# EEPROM_shield.net
KiCad netlist of a schematic drawn in EAGLE
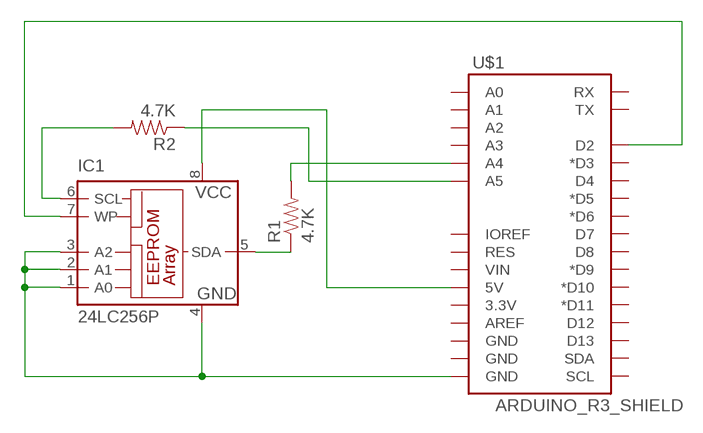
[diagram p0: schematic, sheet 1]

(export (version "E")
  (design (tool "Eeschema 10.0.6"))
  (components
    (comp (ref "IC1")
      (value "24LC256P")
      (footprint "eagle-import:DIL8")
      (fields (field (name "MF") "MICROCHIP") (field (name "MPN") "24LC256-E/P"))
      (libsource (lib "eagle-import") (part "24PLC256"))
    )
    (comp (ref "R1")
      (value "4.7K")
      (footprint "eagle-import:AXIAL-0.4")
      (libsource (lib "eagle-import") (part "RESISTORPTH-1/4W"))
    )
    (comp (ref "R2")
      (value "4.7K")
      (footprint "eagle-import:AXIAL-0.4")
      (libsource (lib "eagle-import") (part "RESISTORPTH-1/4W"))
    )
    (comp (ref "U$1")
      (value "ARDUINO_R3_SHIELD")
      (footprint "eagle-import:UNO_R3_SHIELD")
      (libsource (lib "eagle-import") (part "ARDUINO_R3_SHIELD"))
    )
  )
  (nets
    (net (code "1") (name "Net-(IC1-A0)") (class "Default")
      (node (ref "IC1") (pin "1") (pinfunction "A0_1") (pintype "input"))
      (node (ref "IC1") (pin "2") (pinfunction "A1_2") (pintype "input"))
      (node (ref "IC1") (pin "3") (pinfunction "A2_3") (pintype "input"))
      (node (ref "IC1") (pin "4") (pinfunction "GND_4") (pintype "power_in"))
      (node (ref "U$1") (pin "GND@0") (pinfunction "GND_GND@0") (pintype "bidirectional"))
    )
    (net (code "2") (name "Net-(IC1-SCL)") (class "Default")
      (node (ref "IC1") (pin "6") (pinfunction "SCL_6") (pintype "input"))
      (node (ref "R2") (pin "P$2") (pinfunction "2_P$2") (pintype "passive"))
    )
    (net (code "3") (name "Net-(IC1-SDA)") (class "Default")
      (node (ref "IC1") (pin "5") (pinfunction "SDA_5") (pintype "bidirectional"))
      (node (ref "R1") (pin "P$1") (pinfunction "1_P$1") (pintype "passive"))
    )
    (net (code "4") (name "Net-(IC1-VCC)") (class "Default")
      (node (ref "IC1") (pin "8") (pinfunction "VCC_8") (pintype "power_in"))
      (node (ref "U$1") (pin "5V") (pinfunction "5V_5V") (pintype "bidirectional"))
    )
    (net (code "5") (name "Net-(IC1-WP)") (class "Default")
      (node (ref "IC1") (pin "7") (pinfunction "WP_7") (pintype "input"))
      (node (ref "U$1") (pin "D2") (pinfunction "D2_D2") (pintype "bidirectional"))
    )
    (net (code "6") (name "Net-(R1-2)") (class "Default")
      (node (ref "R1") (pin "P$2") (pinfunction "2_P$2") (pintype "passive"))
      (node (ref "U$1") (pin "A4") (pinfunction "A4_A4") (pintype "bidirectional"))
    )
    (net (code "7") (name "Net-(R2-1)") (class "Default")
      (node (ref "R2") (pin "P$1") (pinfunction "1_P$1") (pintype "passive"))
      (node (ref "U$1") (pin "A5") (pinfunction "A5_A5") (pintype "bidirectional"))
    )
    (net (code "8") (name "unconnected-(U$1-*D3-PadD3)") (class "Default")
      (node (ref "U$1") (pin "D3") (pinfunction "*D3_D3") (pintype "bidirectional"))
    )
    (net (code "9") (name "unconnected-(U$1-*D5-PadD5)") (class "Default")
      (node (ref "U$1") (pin "D5") (pinfunction "*D5_D5") (pintype "bidirectional"))
    )
    (net (code "10") (name "unconnected-(U$1-*D6-PadD6)") (class "Default")
      (node (ref "U$1") (pin "D6") (pinfunction "*D6_D6") (pintype "bidirectional"))
    )
    (net (code "11") (name "unconnected-(U$1-*D9-PadD9)") (class "Default")
      (node (ref "U$1") (pin "D9") (pinfunction "*D9_D9") (pintype "bidirectional"))
    )
    (net (code "12") (name "unconnected-(U$1-*D10-PadD10)") (class "Default")
      (node (ref "U$1") (pin "D10") (pinfunction "*D10_D10") (pintype "bidirectional"))
    )
    (net (code "13") (name "unconnected-(U$1-*D11-PadD11)") (class "Default")
      (node (ref "U$1") (pin "D11") (pinfunction "*D11_D11") (pintype "bidirectional"))
    )
    (net (code "14") (name "unconnected-(U$1-GND-PadGND@1)") (class "Default")
      (node (ref "U$1") (pin "GND@1") (pinfunction "GND_GND@1") (pintype "bidirectional"))
    )
    (net (code "15") (name "unconnected-(U$1-GND-PadGND@2)") (class "Default")
      (node (ref "U$1") (pin "GND@2") (pinfunction "GND_GND@2") (pintype "bidirectional"))
    )
    (net (code "16") (name "unconnected-(U$1-Pad3.3V)") (class "Default")
      (node (ref "U$1") (pin "3.3V") (pinfunction "3.3V_3.3V") (pintype "bidirectional"))
    )
    (net (code "17") (name "unconnected-(U$1-PadA0)") (class "Default")
      (node (ref "U$1") (pin "A0") (pinfunction "A0_A0") (pintype "bidirectional"))
    )
    (net (code "18") (name "unconnected-(U$1-PadA1)") (class "Default")
      (node (ref "U$1") (pin "A1") (pinfunction "A1_A1") (pintype "bidirectional"))
    )
    (net (code "19") (name "unconnected-(U$1-PadA2)") (class "Default")
      (node (ref "U$1") (pin "A2") (pinfunction "A2_A2") (pintype "bidirectional"))
    )
    (net (code "20") (name "unconnected-(U$1-PadA3)") (class "Default")
      (node (ref "U$1") (pin "A3") (pinfunction "A3_A3") (pintype "bidirectional"))
    )
    (net (code "21") (name "unconnected-(U$1-PadAREF)") (class "Default")
      (node (ref "U$1") (pin "AREF") (pinfunction "AREF_AREF") (pintype "bidirectional"))
    )
    (net (code "22") (name "unconnected-(U$1-PadD4)") (class "Default")
      (node (ref "U$1") (pin "D4") (pinfunction "D4_D4") (pintype "bidirectional"))
    )
    (net (code "23") (name "unconnected-(U$1-PadD7)") (class "Default")
      (node (ref "U$1") (pin "D7") (pinfunction "D7_D7") (pintype "bidirectional"))
    )
    (net (code "24") (name "unconnected-(U$1-PadD8)") (class "Default")
      (node (ref "U$1") (pin "D8") (pinfunction "D8_D8") (pintype "bidirectional"))
    )
    (net (code "25") (name "unconnected-(U$1-PadD12)") (class "Default")
      (node (ref "U$1") (pin "D12") (pinfunction "D12_D12") (pintype "bidirectional"))
    )
    (net (code "26") (name "unconnected-(U$1-PadD13)") (class "Default")
      (node (ref "U$1") (pin "D13") (pinfunction "D13_D13") (pintype "bidirectional"))
    )
    (net (code "27") (name "unconnected-(U$1-PadIOREF)") (class "Default")
      (node (ref "U$1") (pin "IOREF") (pinfunction "IOREF_IOREF") (pintype "bidirectional"))
    )
    (net (code "28") (name "unconnected-(U$1-PadRES)") (class "Default")
      (node (ref "U$1") (pin "RES") (pinfunction "RES_RES") (pintype "bidirectional"))
    )
    (net (code "29") (name "unconnected-(U$1-PadRX)") (class "Default")
      (node (ref "U$1") (pin "RX") (pinfunction "RX_RX") (pintype "bidirectional"))
    )
    (net (code "30") (name "unconnected-(U$1-PadSCL)") (class "Default")
      (node (ref "U$1") (pin "SCL") (pinfunction "SCL_SCL") (pintype "bidirectional"))
    )
    (net (code "31") (name "unconnected-(U$1-PadSDA)") (class "Default")
      (node (ref "U$1") (pin "SDA") (pinfunction "SDA_SDA") (pintype "bidirectional"))
    )
    (net (code "32") (name "unconnected-(U$1-PadTX)") (class "Default")
      (node (ref "U$1") (pin "TX") (pinfunction "TX_TX") (pintype "bidirectional"))
    )
    (net (code "33") (name "unconnected-(U$1-PadVIN)") (class "Default")
      (node (ref "U$1") (pin "VIN") (pinfunction "VIN_VIN") (pintype "bidirectional"))
    )
  )
)
